# PCB_WeMosD1_IoT.net
KiCad netlist of a schematic drawn in Altium Designer
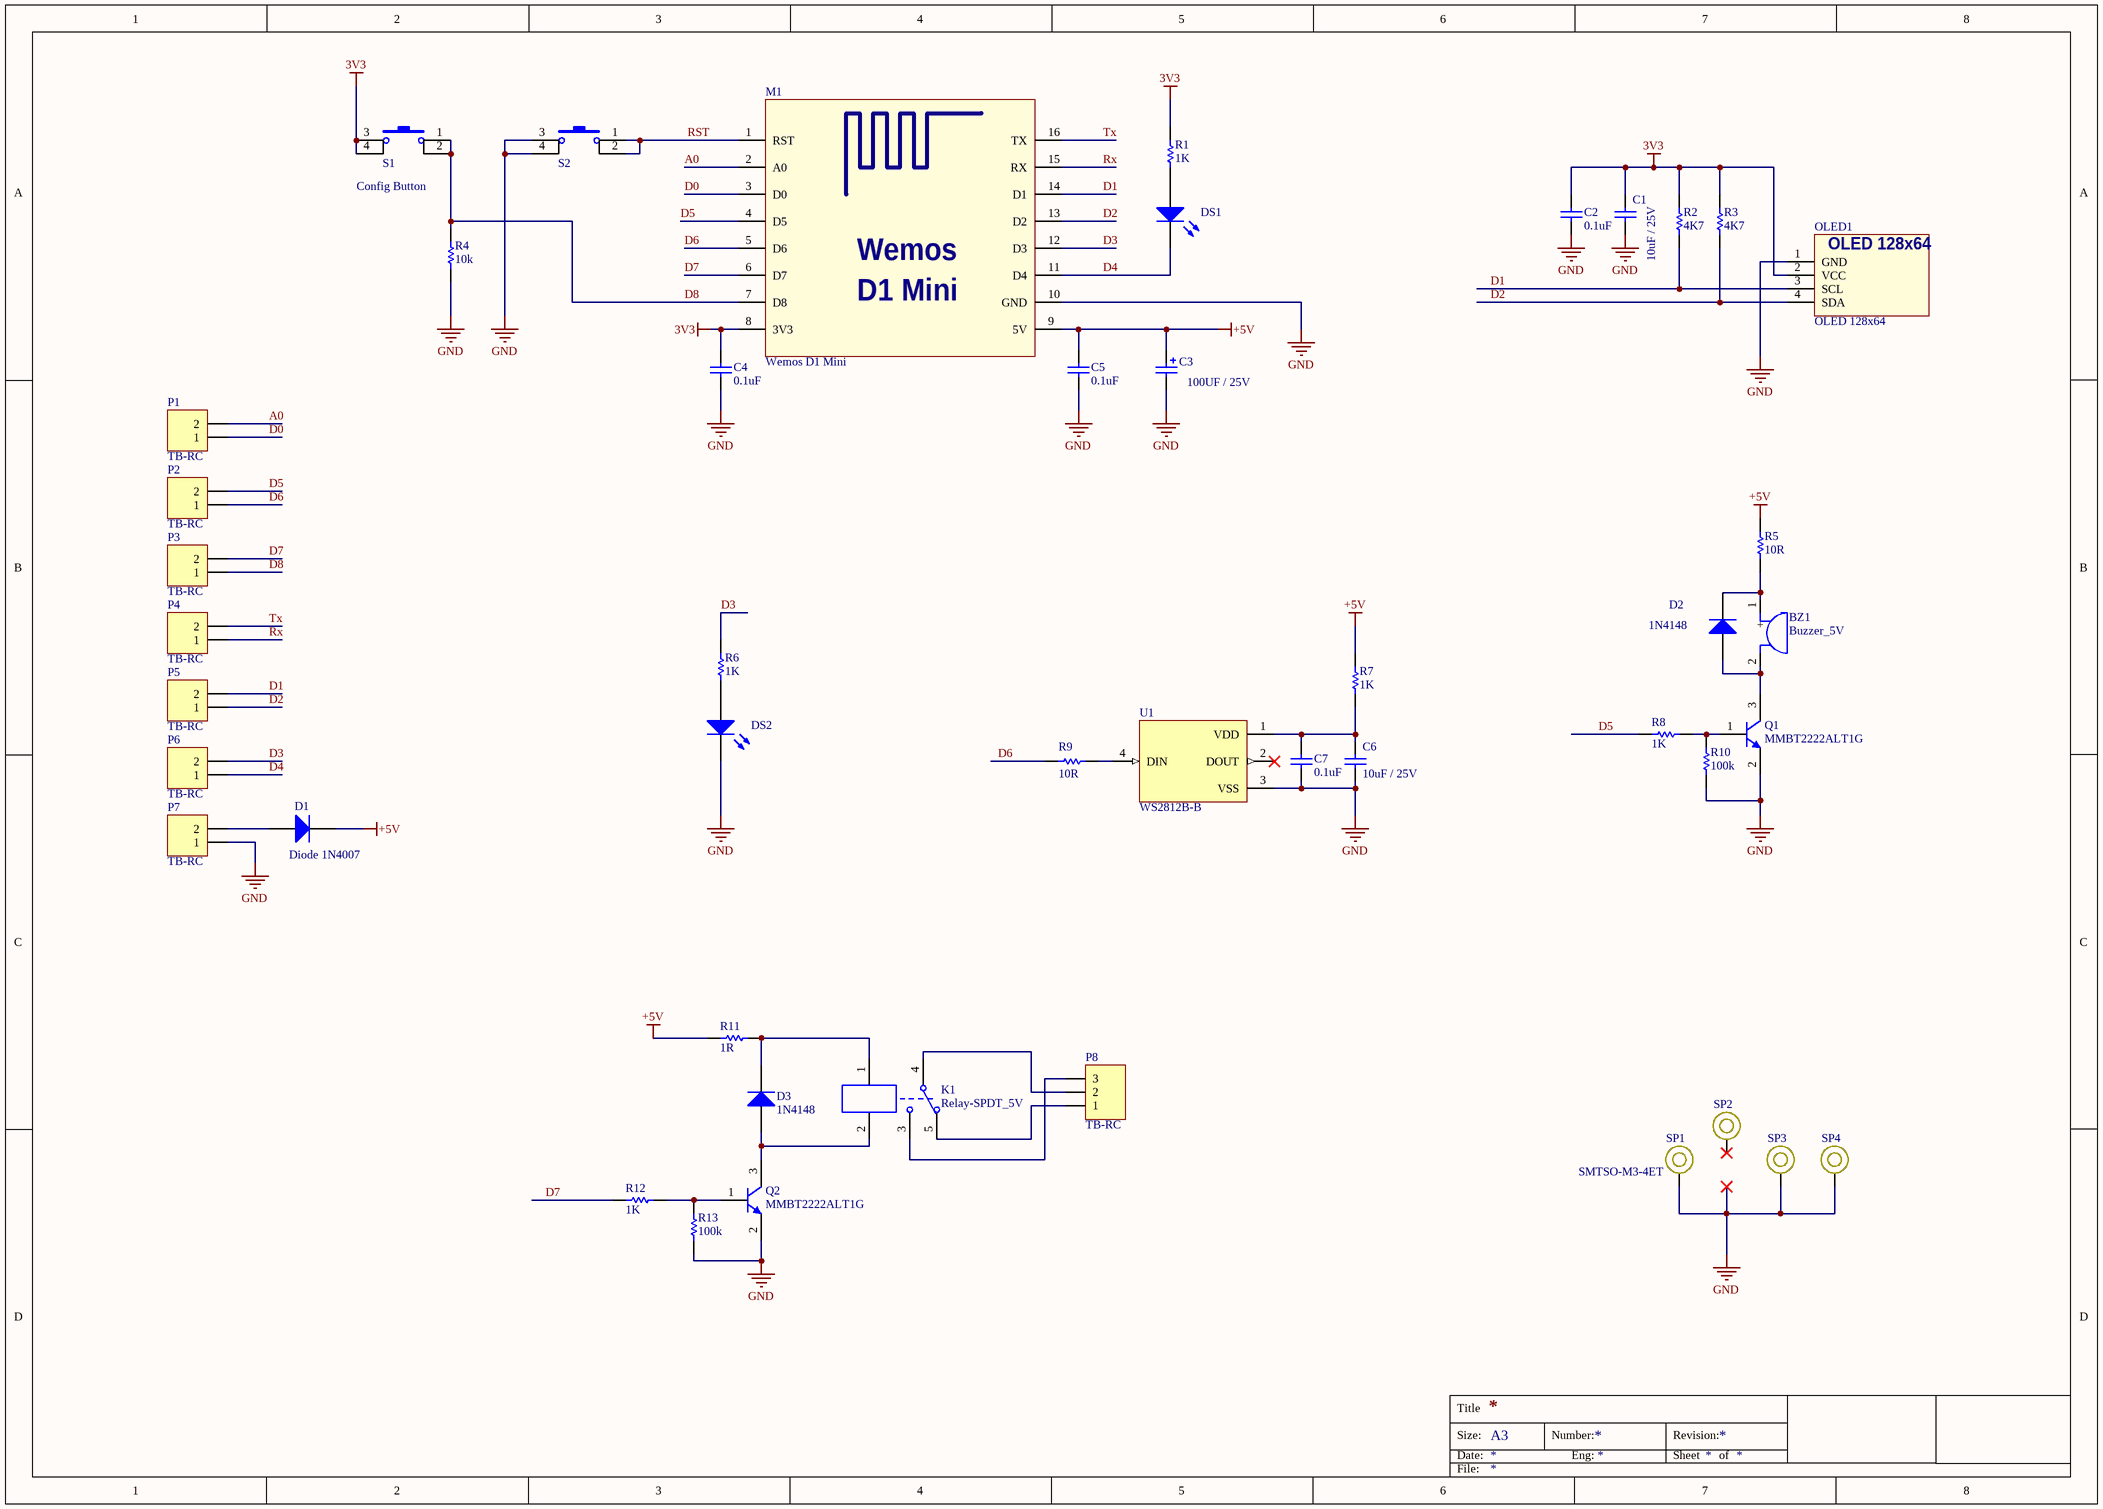
[diagram p0: PCB_WeMosD1_IoT.SchDoc]

(export (version "E")
  (design (tool "Eeschema 10.0.6"))
  (components
    (comp (ref "BZ1")
      (value "Buzzer_5V")
      (footprint "N_20170921:Buzzer_5V")
      (fields (field (name "MANUFACTURER") "Jiangsu Huaneng Elec"))
      (libsource (lib "N_20170921") (part "Buzzer_5V"))
    )
    (comp (ref "C1")
      (value "10uF / 25V")
      (footprint "CAPC2012L")
      (description "CAP CER 10UF 16V X5R 0805")
      (fields (field (name "MANUFACTURER") "Yageo"))
      (libsource (lib "Miscellaneous Devices") (part "Cap Semi"))
    )
    (comp (ref "C2")
      (value "0.1uF")
      (footprint "CAPC1608L")
      (description "Capacitor Ceramic 0.10uF 10% 16V X7R 0603")
      (fields (field (name "MANUFACTURER") "Yageo"))
      (libsource (lib "BarcodeReaderGSM_PCB_v1_0_2") (part "Cap Semi_2"))
    )
    (comp (ref "C3")
      (value "100UF / 25V")
      (footprint "100UF / 25V")
      (description "CAP ALUM 100UF 20% 25V RADIAL")
      (fields
        (field (name "MANUFACTURER") "United Chemi-Con")
        (field (name "Comment") "Cap Radial 100UF 25V")
      )
      (libsource (lib "TNY288PG_12V_1A") (part "Cap Pol 100UF / 25V"))
    )
    (comp (ref "C4")
      (value "0.1uF")
      (footprint "CAPC1608L")
      (description "Capacitor Ceramic 0.10uF 10% 16V X7R 0603")
      (fields (field (name "MANUFACTURER") "Yageo"))
      (libsource (lib "BarcodeReaderGSM_PCB_v1_0_2") (part "Cap Semi_2"))
    )
    (comp (ref "C5")
      (value "0.1uF")
      (footprint "CAPC1608L")
      (description "Capacitor Ceramic 0.10uF 10% 16V X7R 0603")
      (fields (field (name "MANUFACTURER") "Yageo"))
      (libsource (lib "BarcodeReaderGSM_PCB_v1_0_2") (part "Cap Semi_2"))
    )
    (comp (ref "C6")
      (value "10uF / 25V")
      (footprint "CAPC2012L")
      (description "CAP CER 10UF 16V X5R 0805")
      (fields (field (name "MANUFACTURER") "Yageo"))
      (libsource (lib "Miscellaneous Devices") (part "Cap Semi"))
    )
    (comp (ref "C7")
      (value "0.1uF")
      (footprint "CAPC1608L")
      (description "Capacitor Ceramic 0.10uF 10% 16V X7R 0603")
      (fields (field (name "MANUFACTURER") "Yageo"))
      (libsource (lib "BarcodeReaderGSM_PCB_v1_0_2") (part "Cap Semi_2"))
    )
    (comp (ref "D1")
      (value "Diode 1N4007")
      (footprint "DO-41")
      (description "1 Amp General Purpose Rectifier")
      (fields (field (name "PUBLISHER") "Altium Limited"))
      (libsource (lib "Miscellaneous Devices") (part "Diode 1N4007"))
    )
    (comp (ref "D2")
      (value "1N4148")
      (footprint "MELF-D3513-1405")
      (description "DIODE GEN PURP 100V 200MA SOD80")
      (fields (field (name "MANUFACTURER") "ON Semiconductor"))
      (libsource (lib "TC_Dim&2Way_PCB") (part "Diode 1N4148"))
    )
    (comp (ref "D3")
      (value "1N4148")
      (footprint "MELF-D3513-1405")
      (description "DIODE GEN PURP 100V 200MA SOD80")
      (fields (field (name "MANUFACTURER") "ON Semiconductor"))
      (libsource (lib "TC_Dim&2Way_PCB") (part "Diode 1N4148"))
    )
    (comp (ref "DS1")
      (value "LED RED 3MM")
      (footprint "LED Red 3MM")
      (libsource (lib "N_20170921") (part "LED_Red_3MM"))
    )
    (comp (ref "DS2")
      (value "LED GREEN")
      (footprint "LEDC2012X120N_SML-LXT0805IW-TR(Primary)")
      (description "LED GREEN CLEAR 0805 SMD")
      (fields (field (name "MANUFACTURER") "Rohm Semiconductor"))
      (libsource (lib "N_20170921") (part "LED_Blue"))
    )
    (comp (ref "K1")
      (value "Relay-SPDT_5V")
      (footprint "Relay-SPDT_5V")
      (description "Single-Pole Dual-Throw Relay")
      (fields (field (name "PUBLISHER") "Altium Limited"))
      (libsource (lib "N_20170921") (part "Relay-SPDT"))
    )
    (comp (ref "M1")
      (value "Wemos D1 Mini")
      (footprint "Wemos D1 Mini")
      (libsource (lib "N_20170921") (part "Wemos_d1_mini_module"))
    )
    (comp (ref "OLED1")
      (value "OLED 128x64")
      (footprint "N_20170921:OLED display 128x64")
      (description "OLED Display 128x64")
      (libsource (lib "N_20170921") (part "OLED_128x64"))
    )
    (comp (ref "P1")
      (value "TB-RC")
      (footprint "2-Pin TB Rising Clamp Vertical")
      (description "TERMINAL BLOCK 5.08MM 2POS PCB Rising Clamp")
      (libsource (lib "N_20170921") (part "TB-2_Rising Clamp"))
    )
    (comp (ref "P2")
      (value "TB-RC")
      (footprint "2-Pin TB Rising Clamp Vertical")
      (description "TERMINAL BLOCK 5.08MM 2POS PCB Rising Clamp")
      (libsource (lib "N_20170921") (part "TB-2_Rising Clamp"))
    )
    (comp (ref "P3")
      (value "TB-RC")
      (footprint "2-Pin TB Rising Clamp Vertical")
      (description "TERMINAL BLOCK 5.08MM 2POS PCB Rising Clamp")
      (libsource (lib "N_20170921") (part "TB-2_Rising Clamp"))
    )
    (comp (ref "P4")
      (value "TB-RC")
      (footprint "2-Pin TB Rising Clamp Vertical")
      (description "TERMINAL BLOCK 5.08MM 2POS PCB Rising Clamp")
      (libsource (lib "N_20170921") (part "TB-2_Rising Clamp"))
    )
    (comp (ref "P5")
      (value "TB-RC")
      (footprint "2-Pin TB Rising Clamp Vertical")
      (description "TERMINAL BLOCK 5.08MM 2POS PCB Rising Clamp")
      (libsource (lib "N_20170921") (part "TB-2_Rising Clamp"))
    )
    (comp (ref "P6")
      (value "TB-RC")
      (footprint "2-Pin TB Rising Clamp Vertical")
      (description "TERMINAL BLOCK 5.08MM 2POS PCB Rising Clamp")
      (libsource (lib "N_20170921") (part "TB-2_Rising Clamp"))
    )
    (comp (ref "P7")
      (value "TB-RC")
      (footprint "2-Pin TB Rising Clamp Vertical")
      (description "TERMINAL BLOCK 5.08MM 2POS PCB Rising Clamp")
      (libsource (lib "N_20170921") (part "TB-2_Rising Clamp"))
    )
    (comp (ref "P8")
      (value "TB-RC")
      (footprint "3-Pin TB Rising Clamp Vertical")
      (description "TERMINAL BLOCK 5.08MM 3POS PCB Rising Clamp")
      (fields (field (name "MANUFACTURER") "Cixi Kefa Elec"))
      (libsource (lib "N_20170921") (part "TB-3_Rising Clamp"))
    )
    (comp (ref "Q1")
      (value "MMBT2222ALT1G")
      (footprint "SOT23-3L")
      (description "TRANS NPN 40V 0.6A SOT23")
      (fields (field (name "MANUFACTURER") "ON Semiconductor"))
      (libsource (lib "PS_UK") (part "BC849C"))
    )
    (comp (ref "Q2")
      (value "MMBT2222ALT1G")
      (footprint "SOT23-3L")
      (description "TRANS NPN 40V 0.6A SOT23")
      (fields (field (name "MANUFACTURER") "ON Semiconductor"))
      (libsource (lib "PS_UK") (part "BC849C"))
    )
    (comp (ref "R1")
      (value "1K")
      (footprint "N_20170921:RESC1608X05L(0603)")
      (description "RES SMD 1K OHM 1% 1/10W 0603")
      (fields (field (name "MANUFACTURER") "Yageo") (field (name "Comment") "Res 0603"))
      (libsource (lib "Miscellaneous Devices") (part "Res1"))
    )
    (comp (ref "R2")
      (value "4K7")
      (footprint "N_20170921:RESC1608X05L(0603)")
      (description "RES SMD 4.7K OHM 1% 1/10W 0603")
      (fields (field (name "MANUFACTURER") "Yageo") (field (name "Comment") "Res 0603"))
      (libsource (lib "BarcodeReaderGSM_PCB_v1_0_2") (part "Res1"))
    )
    (comp (ref "R3")
      (value "4K7")
      (footprint "N_20170921:RESC1608X05L(0603)")
      (description "RES SMD 4.7K OHM 1% 1/10W 0603")
      (fields (field (name "MANUFACTURER") "Yageo") (field (name "Comment") "Res 0603"))
      (libsource (lib "BarcodeReaderGSM_PCB_v1_0_2") (part "Res1"))
    )
    (comp (ref "R4")
      (value "10k")
      (footprint "N_20170921:RESC1608X05L(0603)")
      (description "RES SMD 10K OHM 1% 1/10W 0603")
      (fields (field (name "MANUFACTURER") "Yageo") (field (name "Comment") "Res 0603"))
      (libsource (lib "BarcodeReaderGSM_PCB_v1_0_2") (part "Res1"))
    )
    (comp (ref "R5")
      (value "10R")
      (footprint "N_20170921:RESC1608X05L(0603)")
      (description "RES SMD 10OHM 1% 1/10W 0603")
      (fields (field (name "MANUFACTURER") "Yageo") (field (name "Comment") "Res 0603"))
      (libsource (lib "Miscellaneous Devices") (part "Res1"))
    )
    (comp (ref "R6")
      (value "1K")
      (footprint "N_20170921:RESC1608X05L(0603)")
      (description "RES SMD 1K OHM 1% 1/10W 0603")
      (fields (field (name "MANUFACTURER") "Yageo") (field (name "Comment") "Res 0603"))
      (libsource (lib "Miscellaneous Devices") (part "Res1"))
    )
    (comp (ref "R7")
      (value "1K")
      (footprint "N_20170921:RESC1608X05L(0603)")
      (description "RES SMD 1K OHM 1% 1/10W 0603")
      (fields (field (name "MANUFACTURER") "Yageo") (field (name "Comment") "Res 0603"))
      (libsource (lib "Miscellaneous Devices") (part "Res1"))
    )
    (comp (ref "R8")
      (value "1K")
      (footprint "N_20170921:RESC1608X05L(0603)")
      (description "RES SMD 1K OHM 1% 1/10W 0603")
      (fields (field (name "MANUFACTURER") "Yageo") (field (name "Comment") "Res 0603"))
      (libsource (lib "Miscellaneous Devices") (part "Res1"))
    )
    (comp (ref "R9")
      (value "10R")
      (footprint "N_20170921:RESC1608X05L(0603)")
      (description "RES SMD 10OHM 1% 1/10W 0603")
      (fields (field (name "MANUFACTURER") "Yageo") (field (name "Comment") "Res 0603"))
      (libsource (lib "Miscellaneous Devices") (part "Res1"))
    )
    (comp (ref "R10")
      (value "100k")
      (footprint "N_20170921:RESC1608X05L(0603)")
      (description "RES SMD 100K OHM 5% 1/10W 0603")
      (fields (field (name "MANUFACTURER") "Yageo") (field (name "Comment") "Res 0603"))
      (libsource (lib "BarcodeReaderGSM_PCB_v1_0_2") (part "Res1"))
    )
    (comp (ref "R11")
      (value "1R")
      (footprint "RESC3216L")
      (description "RES SMD 1 OHM 1% 1/4W 1206")
      (fields (field (name "MANUFACTURER") "Yageo") (field (name "Comment") "Res 1206"))
      (libsource (lib "Miscellaneous Devices") (part "Res1"))
    )
    (comp (ref "R12")
      (value "1K")
      (footprint "N_20170921:RESC1608X05L(0603)")
      (description "RES SMD 1K OHM 1% 1/10W 0603")
      (fields (field (name "MANUFACTURER") "Yageo") (field (name "Comment") "Res 0603"))
      (libsource (lib "Miscellaneous Devices") (part "Res1"))
    )
    (comp (ref "R13")
      (value "100k")
      (footprint "N_20170921:RESC1608X05L(0603)")
      (description "RES SMD 100K OHM 5% 1/10W 0603")
      (fields (field (name "MANUFACTURER") "Yageo") (field (name "Comment") "Res 0603"))
      (libsource (lib "BarcodeReaderGSM_PCB_v1_0_2") (part "Res1"))
    )
    (comp (ref "S1")
      (value "SW-PB_TH_9.5MM")
      (footprint "SW_TL1105 SERIES")
      (description "SWITCH TACTILE SPST-NO 0.05A 12V 9.5MM")
      (fields (field (name "MANUFACTURER") "E-Switch"))
      (libsource (lib "N_20170921") (part "SW-PB_TH_9.5MM"))
    )
    (comp (ref "S2")
      (value "SW-PB_TH_9.5MM")
      (footprint "SW_TL1105 SERIES")
      (description "SWITCH TACTILE SPST-NO 0.05A 12V 9.5MM")
      (fields (field (name "MANUFACTURER") "E-Switch"))
      (libsource (lib "N_20170921") (part "SW-PB_TH_9.5MM"))
    )
    (comp (ref "SP1")
      (value "SMTSO-M3-4ET")
      (footprint "SMTSO_M3")
      (description "Standoffs & Spacers SMTSO, M3, THRU-HOLE, CRS, ET")
      (fields (field (name "MANUFACTURER") "PEM"))
      (libsource (lib "N_20170921") (part "SMTSO-M3-4ET"))
    )
    (comp (ref "SP2")
      (value "SMTSO-M3-4ET")
      (footprint "SMTSO_M3")
      (description "Standoffs & Spacers SMTSO, M3, THRU-HOLE, CRS, ET")
      (fields (field (name "MANUFACTURER") "PEM"))
      (libsource (lib "N_20170921") (part "SMTSO-M3-4ET"))
    )
    (comp (ref "SP3")
      (value "SMTSO-M3-4ET")
      (footprint "SMTSO_M3")
      (description "Standoffs & Spacers SMTSO, M3, THRU-HOLE, CRS, ET")
      (fields (field (name "MANUFACTURER") "PEM"))
      (libsource (lib "N_20170921") (part "SMTSO-M3-4ET"))
    )
    (comp (ref "SP4")
      (value "SMTSO-M3-4ET")
      (footprint "SMTSO_M3")
      (description "Standoffs & Spacers SMTSO, M3, THRU-HOLE, CRS, ET")
      (fields (field (name "MANUFACTURER") "PEM"))
      (libsource (lib "N_20170921") (part "SMTSO-M3-4ET"))
    )
    (comp (ref "U1")
      (value "WS2812B-B")
      (footprint "N_20170921:LED_WS2812B-B")
      (description "Intelligent control LED integrated light source")
      (fields (field (name "MF") "Worldsemi"))
      (libsource (lib "N_20170921") (part "WS2812B-B"))
    )
  )
  (nets
    (net (code "1") (name "+5V") (class "Default")
      (node (ref "C3") (pin "1") (pinfunction "1_1") (pintype "passive"))
      (node (ref "C5") (pin "2") (pinfunction "2_2") (pintype "passive"))
      (node (ref "D1") (pin "2") (pinfunction "K_2") (pintype "passive"))
      (node (ref "M1") (pin "9") (pinfunction "5V_9") (pintype "passive"))
      (node (ref "R11") (pin "1") (pinfunction "1_1") (pintype "passive"))
      (node (ref "R5") (pin "2") (pinfunction "2_2") (pintype "passive"))
      (node (ref "R7") (pin "1") (pinfunction "1_1") (pintype "passive"))
    )
    (net (code "2") (name "/A0") (class "Default")
      (node (ref "M1") (pin "2") (pinfunction "A0_2") (pintype "passive"))
      (node (ref "P1") (pin "2") (pinfunction "2_2") (pintype "passive"))
    )
    (net (code "3") (name "/D0") (class "Default")
      (node (ref "M1") (pin "3") (pinfunction "D0_3") (pintype "passive"))
      (node (ref "P1") (pin "1") (pinfunction "1_1") (pintype "passive"))
    )
    (net (code "4") (name "/D1") (class "Default")
      (node (ref "M1") (pin "14") (pinfunction "D1_14") (pintype "passive"))
      (node (ref "OLED1") (pin "3") (pinfunction "SCL_3") (pintype "passive"))
      (node (ref "P5") (pin "2") (pinfunction "2_2") (pintype "passive"))
      (node (ref "R2") (pin "2") (pinfunction "2_2") (pintype "passive"))
    )
    (net (code "5") (name "/D2") (class "Default")
      (node (ref "M1") (pin "13") (pinfunction "D2_13") (pintype "passive"))
      (node (ref "OLED1") (pin "4") (pinfunction "SDA_4") (pintype "passive"))
      (node (ref "P5") (pin "1") (pinfunction "1_1") (pintype "passive"))
      (node (ref "R3") (pin "2") (pinfunction "2_2") (pintype "passive"))
    )
    (net (code "6") (name "/D3") (class "Default")
      (node (ref "M1") (pin "12") (pinfunction "D3_12") (pintype "passive"))
      (node (ref "P6") (pin "2") (pinfunction "2_2") (pintype "passive"))
      (node (ref "R6") (pin "2") (pinfunction "2_2") (pintype "passive"))
    )
    (net (code "7") (name "/D4") (class "Default")
      (node (ref "DS1") (pin "2") (pinfunction "K_2") (pintype "passive"))
      (node (ref "M1") (pin "11") (pinfunction "D4_11") (pintype "passive"))
      (node (ref "P6") (pin "1") (pinfunction "1_1") (pintype "passive"))
    )
    (net (code "8") (name "/D5") (class "Default")
      (node (ref "M1") (pin "4") (pinfunction "D5_4") (pintype "passive"))
      (node (ref "P2") (pin "2") (pinfunction "2_2") (pintype "passive"))
      (node (ref "R8") (pin "1") (pinfunction "1_1") (pintype "passive"))
    )
    (net (code "9") (name "/D6") (class "Default")
      (node (ref "M1") (pin "5") (pinfunction "D6_5") (pintype "passive"))
      (node (ref "P2") (pin "1") (pinfunction "1_1") (pintype "passive"))
      (node (ref "R9") (pin "1") (pinfunction "1_1") (pintype "passive"))
    )
    (net (code "10") (name "/D7") (class "Default")
      (node (ref "M1") (pin "6") (pinfunction "D7_6") (pintype "passive"))
      (node (ref "P3") (pin "2") (pinfunction "2_2") (pintype "passive"))
      (node (ref "R12") (pin "1") (pinfunction "1_1") (pintype "passive"))
    )
    (net (code "11") (name "/D8") (class "Default")
      (node (ref "M1") (pin "7") (pinfunction "D8_7") (pintype "passive"))
      (node (ref "P3") (pin "1") (pinfunction "1_1") (pintype "passive"))
      (node (ref "R4") (pin "1") (pinfunction "1_1") (pintype "passive"))
      (node (ref "S1") (pin "1") (pinfunction "1_1") (pintype "passive"))
      (node (ref "S1") (pin "2") (pinfunction "2_2") (pintype "passive"))
    )
    (net (code "12") (name "/RST") (class "Default")
      (node (ref "M1") (pin "1") (pinfunction "RST_1") (pintype "passive"))
      (node (ref "S2") (pin "1") (pinfunction "1_1") (pintype "passive"))
      (node (ref "S2") (pin "2") (pinfunction "2_2") (pintype "passive"))
    )
    (net (code "13") (name "/Rx") (class "Default")
      (node (ref "M1") (pin "15") (pinfunction "RX_15") (pintype "passive"))
      (node (ref "P4") (pin "1") (pinfunction "1_1") (pintype "passive"))
    )
    (net (code "14") (name "/Tx") (class "Default")
      (node (ref "M1") (pin "16") (pinfunction "TX_16") (pintype "passive"))
      (node (ref "P4") (pin "2") (pinfunction "2_2") (pintype "passive"))
    )
    (net (code "15") (name "3V3") (class "Default")
      (node (ref "C1") (pin "2") (pinfunction "2_2") (pintype "passive"))
      (node (ref "C2") (pin "2") (pinfunction "2_2") (pintype "passive"))
      (node (ref "C4") (pin "2") (pinfunction "2_2") (pintype "passive"))
      (node (ref "M1") (pin "8") (pinfunction "3V3_8") (pintype "passive"))
      (node (ref "OLED1") (pin "2") (pinfunction "VCC_2") (pintype "passive"))
      (node (ref "R1") (pin "2") (pinfunction "2_2") (pintype "passive"))
      (node (ref "R2") (pin "1") (pinfunction "1_1") (pintype "passive"))
      (node (ref "R3") (pin "1") (pinfunction "1_1") (pintype "passive"))
      (node (ref "S1") (pin "3") (pinfunction "3_3") (pintype "passive"))
      (node (ref "S1") (pin "4") (pinfunction "4_4") (pintype "passive"))
    )
    (net (code "16") (name "GND") (class "Default")
      (node (ref "C1") (pin "1") (pinfunction "1_1") (pintype "passive"))
      (node (ref "C2") (pin "1") (pinfunction "1_1") (pintype "passive"))
      (node (ref "C3") (pin "2") (pinfunction "2_2") (pintype "passive"))
      (node (ref "C4") (pin "1") (pinfunction "1_1") (pintype "passive"))
      (node (ref "C5") (pin "1") (pinfunction "1_1") (pintype "passive"))
      (node (ref "C6") (pin "1") (pinfunction "1_1") (pintype "passive"))
      (node (ref "C7") (pin "1") (pinfunction "1_1") (pintype "passive"))
      (node (ref "DS2") (pin "C") (pinfunction "C_C") (pintype "passive"))
      (node (ref "M1") (pin "10") (pinfunction "GND_10") (pintype "passive"))
      (node (ref "OLED1") (pin "1") (pinfunction "GND_1") (pintype "passive"))
      (node (ref "P7") (pin "1") (pinfunction "1_1") (pintype "passive"))
      (node (ref "Q1") (pin "2") (pinfunction "E_2") (pintype "passive"))
      (node (ref "Q2") (pin "2") (pinfunction "E_2") (pintype "passive"))
      (node (ref "R10") (pin "2") (pinfunction "2_2") (pintype "passive"))
      (node (ref "R13") (pin "2") (pinfunction "2_2") (pintype "passive"))
      (node (ref "R4") (pin "2") (pinfunction "2_2") (pintype "passive"))
      (node (ref "S2") (pin "3") (pinfunction "3_3") (pintype "passive"))
      (node (ref "S2") (pin "4") (pinfunction "4_4") (pintype "passive"))
      (node (ref "SP1") (pin "0") (pinfunction "0_0") (pintype "passive"))
      (node (ref "SP3") (pin "0") (pinfunction "0_0") (pintype "passive"))
      (node (ref "SP4") (pin "0") (pinfunction "0_0") (pintype "passive"))
      (node (ref "U1") (pin "3") (pinfunction "VSS_3") (pintype "power_in"))
    )
    (net (code "17") (name "Net-(BZ1-+)") (class "Default")
      (node (ref "BZ1") (pin "1") (pinfunction "+_1") (pintype "passive"))
      (node (ref "D2") (pin "2") (pinfunction "K_2") (pintype "passive"))
      (node (ref "R5") (pin "1") (pinfunction "1_1") (pintype "passive"))
    )
    (net (code "18") (name "Net-(BZ1--)") (class "Default")
      (node (ref "BZ1") (pin "2") (pinfunction "-_2") (pintype "passive"))
      (node (ref "D2") (pin "1") (pinfunction "A_1") (pintype "passive"))
      (node (ref "Q1") (pin "3") (pinfunction "C_3") (pintype "passive"))
    )
    (net (code "19") (name "Net-(D1-A)") (class "Default")
      (node (ref "D1") (pin "1") (pinfunction "A_1") (pintype "passive"))
      (node (ref "P7") (pin "2") (pinfunction "2_2") (pintype "passive"))
    )
    (net (code "20") (name "Net-(D3-A)") (class "Default")
      (node (ref "D3") (pin "1") (pinfunction "A_1") (pintype "passive"))
      (node (ref "K1") (pin "2") (pinfunction "2_2") (pintype "passive"))
      (node (ref "Q2") (pin "3") (pinfunction "C_3") (pintype "passive"))
    )
    (net (code "21") (name "Net-(D3-K)") (class "Default")
      (node (ref "D3") (pin "2") (pinfunction "K_2") (pintype "passive"))
      (node (ref "K1") (pin "1") (pinfunction "1_1") (pintype "passive"))
      (node (ref "R11") (pin "2") (pinfunction "2_2") (pintype "passive"))
    )
    (net (code "22") (name "Net-(DS1-A)") (class "Default")
      (node (ref "DS1") (pin "1") (pinfunction "A_1") (pintype "passive"))
      (node (ref "R1") (pin "1") (pinfunction "1_1") (pintype "passive"))
    )
    (net (code "23") (name "Net-(DS2-PadA)") (class "Default")
      (node (ref "DS2") (pin "A") (pinfunction "A_A") (pintype "passive"))
      (node (ref "R6") (pin "1") (pinfunction "1_1") (pintype "passive"))
    )
    (net (code "24") (name "Net-(K1-Pad3)") (class "Default")
      (node (ref "K1") (pin "3") (pinfunction "3_3") (pintype "passive"))
      (node (ref "P8") (pin "3") (pinfunction "3_3") (pintype "passive"))
    )
    (net (code "25") (name "Net-(K1-Pad4)") (class "Default")
      (node (ref "K1") (pin "4") (pinfunction "4_4") (pintype "passive"))
      (node (ref "P8") (pin "2") (pinfunction "2_2") (pintype "passive"))
    )
    (net (code "26") (name "Net-(K1-Pad5)") (class "Default")
      (node (ref "K1") (pin "5") (pinfunction "5_5") (pintype "passive"))
      (node (ref "P8") (pin "1") (pinfunction "1_1") (pintype "passive"))
    )
    (net (code "27") (name "Net-(Q1-B)") (class "Default")
      (node (ref "Q1") (pin "1") (pinfunction "B_1") (pintype "passive"))
      (node (ref "R10") (pin "1") (pinfunction "1_1") (pintype "passive"))
      (node (ref "R8") (pin "2") (pinfunction "2_2") (pintype "passive"))
    )
    (net (code "28") (name "Net-(Q2-B)") (class "Default")
      (node (ref "Q2") (pin "1") (pinfunction "B_1") (pintype "passive"))
      (node (ref "R12") (pin "2") (pinfunction "2_2") (pintype "passive"))
      (node (ref "R13") (pin "1") (pinfunction "1_1") (pintype "passive"))
    )
    (net (code "29") (name "Net-(U1-DIN)") (class "Default")
      (node (ref "R9") (pin "2") (pinfunction "2_2") (pintype "passive"))
      (node (ref "U1") (pin "4") (pinfunction "DIN_4") (pintype "input"))
    )
    (net (code "30") (name "Net-(U1-VDD)") (class "Default")
      (node (ref "C6") (pin "2") (pinfunction "2_2") (pintype "passive"))
      (node (ref "C7") (pin "2") (pinfunction "2_2") (pintype "passive"))
      (node (ref "R7") (pin "2") (pinfunction "2_2") (pintype "passive"))
      (node (ref "U1") (pin "1") (pinfunction "VDD_1") (pintype "power_in"))
    )
    (net (code "31") (name "unconnected-(SP2-Pad0)") (class "Default")
      (node (ref "SP2") (pin "0") (pinfunction "0_0") (pintype "passive+no_connect"))
    )
    (net (code "32") (name "unconnected-(U1-DOUT-Pad2)") (class "Default")
      (node (ref "U1") (pin "2") (pinfunction "DOUT_2") (pintype "output+no_connect"))
    )
  )
)
